# nola5.net
KiCad netlist of a schematic drawn in EAGLE
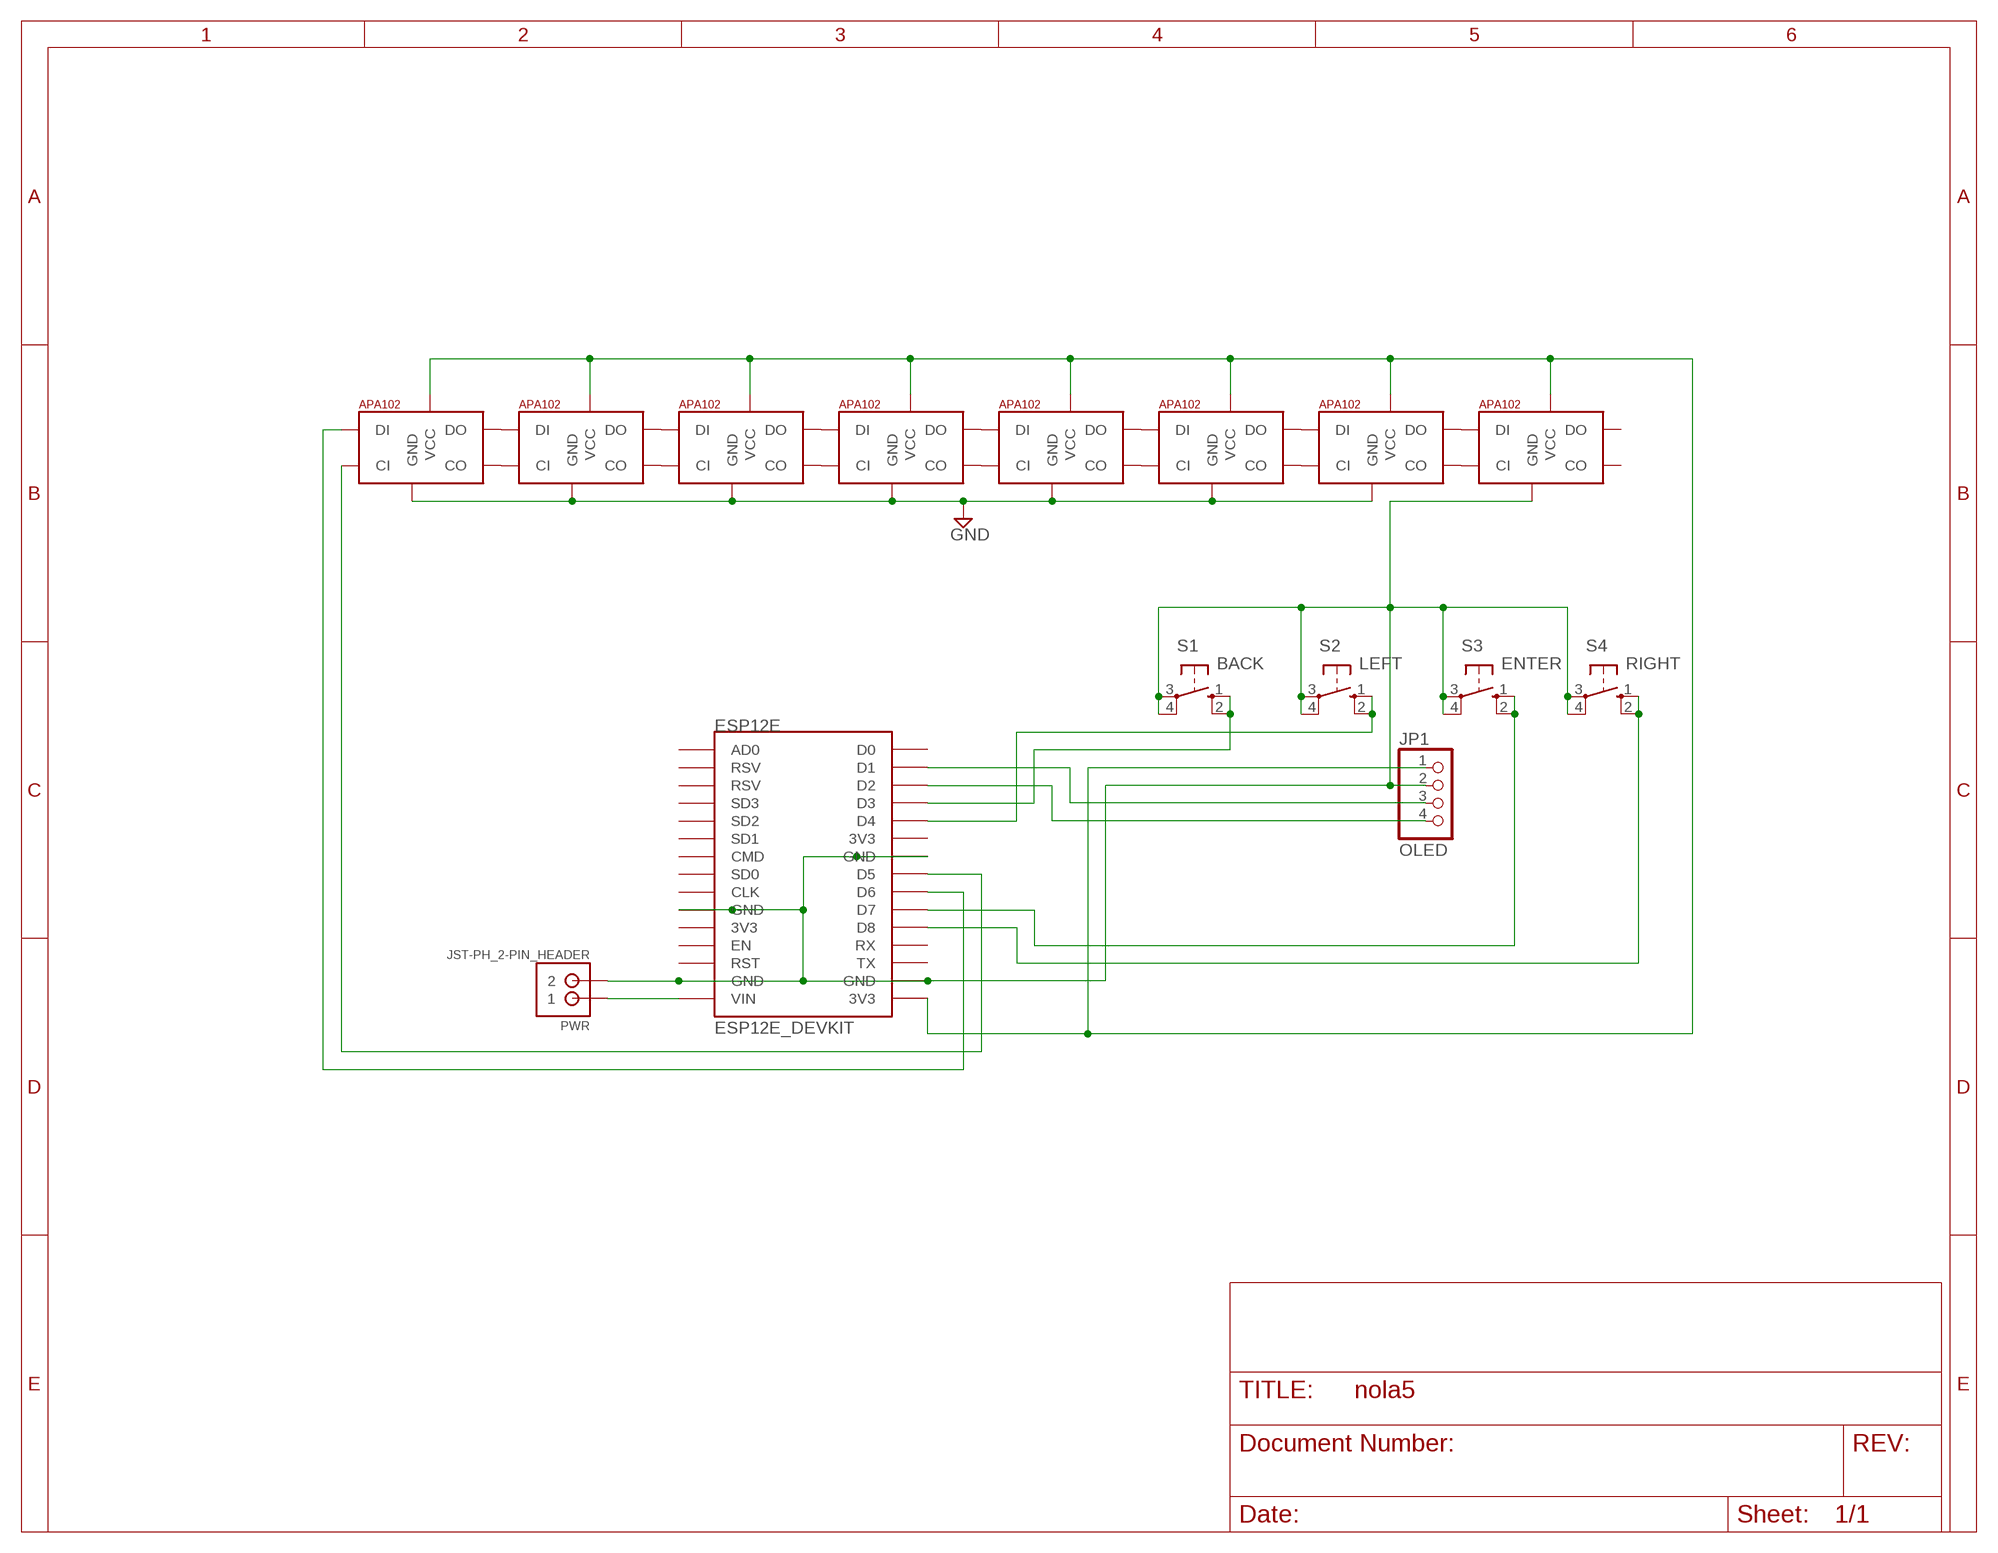
[diagram p0: schematic, sheet 1]

(export (version "E")
  (design (tool "Eeschema 10.0.6"))
  (components
    (comp (ref "ESP12E")
      (value "ESP12E_DEVKIT")
      (footprint "eagle-import:ESP12E_DEVKIT")
      (libsource (lib "eagle-import") (part "ESP12E_DEVKIT"))
    )
    (comp (ref "JP1")
      (value "OLED")
      (footprint "eagle-import:1X04")
      (libsource (lib "eagle-import") (part "PINHD-1X4"))
    )
    (comp (ref "LED1")
      (value "APA1025050")
      (footprint "eagle-import:APA102_5050")
      (libsource (lib "eagle-import") (part "APA1025050"))
    )
    (comp (ref "LED2")
      (value "APA1025050")
      (footprint "eagle-import:APA102_5050")
      (libsource (lib "eagle-import") (part "APA1025050"))
    )
    (comp (ref "LED3")
      (value "APA1025050")
      (footprint "eagle-import:APA102_5050")
      (libsource (lib "eagle-import") (part "APA1025050"))
    )
    (comp (ref "LED4")
      (value "APA1025050")
      (footprint "eagle-import:APA102_5050")
      (libsource (lib "eagle-import") (part "APA1025050"))
    )
    (comp (ref "LED5")
      (value "APA1025050")
      (footprint "eagle-import:APA102_5050")
      (libsource (lib "eagle-import") (part "APA1025050"))
    )
    (comp (ref "LED6")
      (value "APA1025050")
      (footprint "eagle-import:APA102_5050")
      (libsource (lib "eagle-import") (part "APA1025050"))
    )
    (comp (ref "LED7")
      (value "APA1025050")
      (footprint "eagle-import:APA102_5050")
      (libsource (lib "eagle-import") (part "APA1025050"))
    )
    (comp (ref "LED8")
      (value "APA1025050")
      (footprint "eagle-import:APA102_5050")
      (libsource (lib "eagle-import") (part "APA1025050"))
    )
    (comp (ref "PWR")
      (value "JST-PH_2-PIN_HEADER")
      (footprint "eagle-import:JST_B2B-PH_HEADER")
      (libsource (lib "eagle-import") (part "JST-PH_2-PIN_HEADER"))
    )
    (comp (ref "S1")
      (value "BACK")
      (footprint "eagle-import:B3F-10XX")
      (fields (field (name "MPN") "B3F-1000"))
      (libsource (lib "eagle-import") (part "10-XX"))
    )
    (comp (ref "S2")
      (value "LEFT")
      (footprint "eagle-import:B3F-10XX")
      (fields (field (name "MPN") "B3F-1000"))
      (libsource (lib "eagle-import") (part "10-XX"))
    )
    (comp (ref "S3")
      (value "ENTER")
      (footprint "eagle-import:B3F-10XX")
      (fields (field (name "MPN") "B3F-1000"))
      (libsource (lib "eagle-import") (part "10-XX"))
    )
    (comp (ref "S4")
      (value "RIGHT")
      (footprint "eagle-import:B3F-10XX")
      (fields (field (name "MPN") "B3F-1000"))
      (libsource (lib "eagle-import") (part "10-XX"))
    )
  )
  (nets
    (net (code "1") (name "GND") (class "Default")
      (node (ref "ESP12E") (pin "GND@0") (pinfunction "GND_GND@0") (pintype "bidirectional"))
      (node (ref "ESP12E") (pin "GND@1") (pinfunction "GND_GND@1") (pintype "bidirectional"))
      (node (ref "ESP12E") (pin "GND@2") (pinfunction "GND_GND@2") (pintype "bidirectional"))
      (node (ref "ESP12E") (pin "GND@3") (pinfunction "GND_GND@3") (pintype "bidirectional"))
      (node (ref "JP1") (pin "2") (pinfunction "2_2") (pintype "passive"))
      (node (ref "LED1") (pin "6") (pinfunction "GND_6") (pintype "bidirectional"))
      (node (ref "LED2") (pin "6") (pinfunction "GND_6") (pintype "bidirectional"))
      (node (ref "LED3") (pin "6") (pinfunction "GND_6") (pintype "bidirectional"))
      (node (ref "LED4") (pin "6") (pinfunction "GND_6") (pintype "bidirectional"))
      (node (ref "LED5") (pin "6") (pinfunction "GND_6") (pintype "bidirectional"))
      (node (ref "LED6") (pin "6") (pinfunction "GND_6") (pintype "bidirectional"))
      (node (ref "LED7") (pin "6") (pinfunction "GND_6") (pintype "bidirectional"))
      (node (ref "LED8") (pin "6") (pinfunction "GND_6") (pintype "bidirectional"))
      (node (ref "PWR") (pin "P2") (pinfunction "2_P2") (pintype "bidirectional"))
      (node (ref "S1") (pin "3") (pinfunction "P_3") (pintype "passive"))
      (node (ref "S1") (pin "4") (pinfunction "P1_4") (pintype "passive"))
      (node (ref "S2") (pin "3") (pinfunction "P_3") (pintype "passive"))
      (node (ref "S2") (pin "4") (pinfunction "P1_4") (pintype "passive"))
      (node (ref "S3") (pin "3") (pinfunction "P_3") (pintype "passive"))
      (node (ref "S3") (pin "4") (pinfunction "P1_4") (pintype "passive"))
      (node (ref "S4") (pin "3") (pinfunction "P_3") (pintype "passive"))
      (node (ref "S4") (pin "4") (pinfunction "P1_4") (pintype "passive"))
    )
    (net (code "2") (name "Net-(ESP12E-PadD1)") (class "Default")
      (node (ref "ESP12E") (pin "D1") (pinfunction "D1_D1") (pintype "bidirectional"))
      (node (ref "JP1") (pin "3") (pinfunction "3_3") (pintype "passive"))
    )
    (net (code "3") (name "Net-(ESP12E-PadD2)") (class "Default")
      (node (ref "ESP12E") (pin "D2") (pinfunction "D2_D2") (pintype "bidirectional"))
      (node (ref "JP1") (pin "4") (pinfunction "4_4") (pintype "passive"))
    )
    (net (code "4") (name "Net-(LED1-CI)") (class "Default")
      (node (ref "ESP12E") (pin "D5") (pinfunction "D5_D5") (pintype "bidirectional"))
      (node (ref "LED1") (pin "5") (pinfunction "CI_5") (pintype "bidirectional"))
    )
    (net (code "5") (name "Net-(LED1-CO)") (class "Default")
      (node (ref "LED1") (pin "2") (pinfunction "CO_2") (pintype "bidirectional"))
      (node (ref "LED2") (pin "5") (pinfunction "CI_5") (pintype "bidirectional"))
    )
    (net (code "6") (name "Net-(LED1-DI)") (class "Default")
      (node (ref "ESP12E") (pin "D6") (pinfunction "D6_D6") (pintype "bidirectional"))
      (node (ref "LED1") (pin "4") (pinfunction "DI_4") (pintype "bidirectional"))
    )
    (net (code "7") (name "Net-(LED1-DO)") (class "Default")
      (node (ref "LED1") (pin "3") (pinfunction "DO_3") (pintype "bidirectional"))
      (node (ref "LED2") (pin "4") (pinfunction "DI_4") (pintype "bidirectional"))
    )
    (net (code "8") (name "Net-(LED1-VCC)") (class "Default")
      (node (ref "ESP12E") (pin "3V3@2") (pinfunction "3V3_3V3@2") (pintype "bidirectional"))
      (node (ref "JP1") (pin "1") (pinfunction "1_1") (pintype "passive"))
      (node (ref "LED1") (pin "1") (pinfunction "VCC_1") (pintype "bidirectional"))
      (node (ref "LED2") (pin "1") (pinfunction "VCC_1") (pintype "bidirectional"))
      (node (ref "LED3") (pin "1") (pinfunction "VCC_1") (pintype "bidirectional"))
      (node (ref "LED4") (pin "1") (pinfunction "VCC_1") (pintype "bidirectional"))
      (node (ref "LED5") (pin "1") (pinfunction "VCC_1") (pintype "bidirectional"))
      (node (ref "LED6") (pin "1") (pinfunction "VCC_1") (pintype "bidirectional"))
      (node (ref "LED7") (pin "1") (pinfunction "VCC_1") (pintype "bidirectional"))
      (node (ref "LED8") (pin "1") (pinfunction "VCC_1") (pintype "bidirectional"))
    )
    (net (code "9") (name "Net-(LED2-CO)") (class "Default")
      (node (ref "LED2") (pin "2") (pinfunction "CO_2") (pintype "bidirectional"))
      (node (ref "LED3") (pin "5") (pinfunction "CI_5") (pintype "bidirectional"))
    )
    (net (code "10") (name "Net-(LED2-DO)") (class "Default")
      (node (ref "LED2") (pin "3") (pinfunction "DO_3") (pintype "bidirectional"))
      (node (ref "LED3") (pin "4") (pinfunction "DI_4") (pintype "bidirectional"))
    )
    (net (code "11") (name "Net-(LED3-CO)") (class "Default")
      (node (ref "LED3") (pin "2") (pinfunction "CO_2") (pintype "bidirectional"))
      (node (ref "LED4") (pin "5") (pinfunction "CI_5") (pintype "bidirectional"))
    )
    (net (code "12") (name "Net-(LED3-DO)") (class "Default")
      (node (ref "LED3") (pin "3") (pinfunction "DO_3") (pintype "bidirectional"))
      (node (ref "LED4") (pin "4") (pinfunction "DI_4") (pintype "bidirectional"))
    )
    (net (code "13") (name "Net-(LED4-CO)") (class "Default")
      (node (ref "LED4") (pin "2") (pinfunction "CO_2") (pintype "bidirectional"))
      (node (ref "LED5") (pin "5") (pinfunction "CI_5") (pintype "bidirectional"))
    )
    (net (code "14") (name "Net-(LED4-DO)") (class "Default")
      (node (ref "LED4") (pin "3") (pinfunction "DO_3") (pintype "bidirectional"))
      (node (ref "LED5") (pin "4") (pinfunction "DI_4") (pintype "bidirectional"))
    )
    (net (code "15") (name "Net-(LED5-CO)") (class "Default")
      (node (ref "LED5") (pin "2") (pinfunction "CO_2") (pintype "bidirectional"))
      (node (ref "LED6") (pin "5") (pinfunction "CI_5") (pintype "bidirectional"))
    )
    (net (code "16") (name "Net-(LED5-DO)") (class "Default")
      (node (ref "LED5") (pin "3") (pinfunction "DO_3") (pintype "bidirectional"))
      (node (ref "LED6") (pin "4") (pinfunction "DI_4") (pintype "bidirectional"))
    )
    (net (code "17") (name "Net-(LED6-CO)") (class "Default")
      (node (ref "LED6") (pin "2") (pinfunction "CO_2") (pintype "bidirectional"))
      (node (ref "LED7") (pin "5") (pinfunction "CI_5") (pintype "bidirectional"))
    )
    (net (code "18") (name "Net-(LED6-DO)") (class "Default")
      (node (ref "LED6") (pin "3") (pinfunction "DO_3") (pintype "bidirectional"))
      (node (ref "LED7") (pin "4") (pinfunction "DI_4") (pintype "bidirectional"))
    )
    (net (code "19") (name "Net-(LED7-CO)") (class "Default")
      (node (ref "LED7") (pin "2") (pinfunction "CO_2") (pintype "bidirectional"))
      (node (ref "LED8") (pin "5") (pinfunction "CI_5") (pintype "bidirectional"))
    )
    (net (code "20") (name "Net-(LED7-DO)") (class "Default")
      (node (ref "LED7") (pin "3") (pinfunction "DO_3") (pintype "bidirectional"))
      (node (ref "LED8") (pin "4") (pinfunction "DI_4") (pintype "bidirectional"))
    )
    (net (code "21") (name "Net-(PWR-1)") (class "Default")
      (node (ref "ESP12E") (pin "VIN") (pinfunction "VIN_VIN") (pintype "bidirectional"))
      (node (ref "PWR") (pin "P1") (pinfunction "1_P1") (pintype "bidirectional"))
    )
    (net (code "22") (name "Net-(S1-S)") (class "Default")
      (node (ref "ESP12E") (pin "D3") (pinfunction "D3_D3") (pintype "bidirectional"))
      (node (ref "S1") (pin "1") (pinfunction "S_1") (pintype "passive"))
      (node (ref "S1") (pin "2") (pinfunction "S1_2") (pintype "passive"))
    )
    (net (code "23") (name "Net-(S2-S)") (class "Default")
      (node (ref "ESP12E") (pin "D4") (pinfunction "D4_D4") (pintype "bidirectional"))
      (node (ref "S2") (pin "1") (pinfunction "S_1") (pintype "passive"))
      (node (ref "S2") (pin "2") (pinfunction "S1_2") (pintype "passive"))
    )
    (net (code "24") (name "Net-(S3-S)") (class "Default")
      (node (ref "ESP12E") (pin "D7") (pinfunction "D7_D7") (pintype "bidirectional"))
      (node (ref "S3") (pin "1") (pinfunction "S_1") (pintype "passive"))
      (node (ref "S3") (pin "2") (pinfunction "S1_2") (pintype "passive"))
    )
    (net (code "25") (name "Net-(S4-S)") (class "Default")
      (node (ref "ESP12E") (pin "D8") (pinfunction "D8_D8") (pintype "bidirectional"))
      (node (ref "S4") (pin "1") (pinfunction "S_1") (pintype "passive"))
      (node (ref "S4") (pin "2") (pinfunction "S1_2") (pintype "passive"))
    )
    (net (code "26") (name "unconnected-(ESP12E-3V3-Pad3V3@0)") (class "Default")
      (node (ref "ESP12E") (pin "3V3@0") (pinfunction "3V3_3V3@0") (pintype "bidirectional"))
    )
    (net (code "27") (name "unconnected-(ESP12E-3V3-Pad3V3@1)") (class "Default")
      (node (ref "ESP12E") (pin "3V3@1") (pinfunction "3V3_3V3@1") (pintype "bidirectional"))
    )
    (net (code "28") (name "unconnected-(ESP12E-PadAD0)") (class "Default")
      (node (ref "ESP12E") (pin "AD0") (pinfunction "AD0_AD0") (pintype "bidirectional"))
    )
    (net (code "29") (name "unconnected-(ESP12E-PadCLK)") (class "Default")
      (node (ref "ESP12E") (pin "CLK") (pinfunction "CLK_CLK") (pintype "bidirectional"))
    )
    (net (code "30") (name "unconnected-(ESP12E-PadCMD)") (class "Default")
      (node (ref "ESP12E") (pin "CMD") (pinfunction "CMD_CMD") (pintype "bidirectional"))
    )
    (net (code "31") (name "unconnected-(ESP12E-PadD0)") (class "Default")
      (node (ref "ESP12E") (pin "D0") (pinfunction "D0_D0") (pintype "bidirectional"))
    )
    (net (code "32") (name "unconnected-(ESP12E-PadEN)") (class "Default")
      (node (ref "ESP12E") (pin "EN") (pinfunction "EN_EN") (pintype "bidirectional"))
    )
    (net (code "33") (name "unconnected-(ESP12E-PadRST)") (class "Default")
      (node (ref "ESP12E") (pin "RST") (pinfunction "RST_RST") (pintype "bidirectional"))
    )
    (net (code "34") (name "unconnected-(ESP12E-PadRX)") (class "Default")
      (node (ref "ESP12E") (pin "RX") (pinfunction "RX_RX") (pintype "bidirectional"))
    )
    (net (code "35") (name "unconnected-(ESP12E-PadSD0)") (class "Default")
      (node (ref "ESP12E") (pin "SD0") (pinfunction "SD0_SD0") (pintype "bidirectional"))
    )
    (net (code "36") (name "unconnected-(ESP12E-PadSD1)") (class "Default")
      (node (ref "ESP12E") (pin "SD1") (pinfunction "SD1_SD1") (pintype "bidirectional"))
    )
    (net (code "37") (name "unconnected-(ESP12E-PadSD2)") (class "Default")
      (node (ref "ESP12E") (pin "SD2") (pinfunction "SD2_SD2") (pintype "bidirectional"))
    )
    (net (code "38") (name "unconnected-(ESP12E-PadSD3)") (class "Default")
      (node (ref "ESP12E") (pin "SD3") (pinfunction "SD3_SD3") (pintype "bidirectional"))
    )
    (net (code "39") (name "unconnected-(ESP12E-PadTX)") (class "Default")
      (node (ref "ESP12E") (pin "TX") (pinfunction "TX_TX") (pintype "bidirectional"))
    )
    (net (code "40") (name "unconnected-(ESP12E-RSV-PadRSV@0)") (class "Default")
      (node (ref "ESP12E") (pin "RSV@0") (pinfunction "RSV_RSV@0") (pintype "bidirectional"))
    )
    (net (code "41") (name "unconnected-(ESP12E-RSV-PadRSV@1)") (class "Default")
      (node (ref "ESP12E") (pin "RSV@1") (pinfunction "RSV_RSV@1") (pintype "bidirectional"))
    )
    (net (code "42") (name "unconnected-(LED8-CO-Pad2)") (class "Default")
      (node (ref "LED8") (pin "2") (pinfunction "CO_2") (pintype "bidirectional"))
    )
    (net (code "43") (name "unconnected-(LED8-DO-Pad3)") (class "Default")
      (node (ref "LED8") (pin "3") (pinfunction "DO_3") (pintype "bidirectional"))
    )
  )
)
